# AD8428_shield.net
KiCad netlist of a schematic drawn in EAGLE
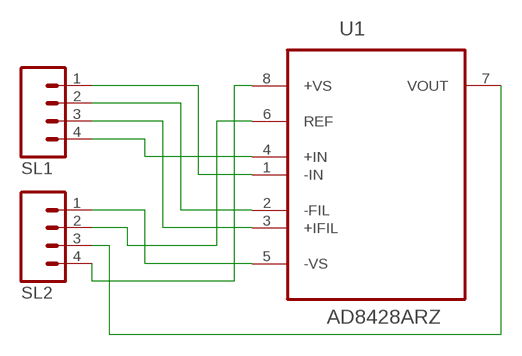
[diagram p0: schematic, sheet 1]

(export (version "E")
  (design (tool "Eeschema 10.0.6"))
  (components
    (comp (ref "SL1")
      (value "M04")
      (footprint "eagle-import:04P")
      (libsource (lib "eagle-import") (part "M04"))
    )
    (comp (ref "SL2")
      (value "M04")
      (footprint "eagle-import:04P")
      (libsource (lib "eagle-import") (part "M04"))
    )
    (comp (ref "U1")
      (value "AD8428ARZ")
      (footprint "eagle-import:SOIC127P600X175-8N")
      (libsource (lib "eagle-import") (part "AD8428ARZ"))
    )
  )
  (nets
    (net (code "1") (name "Net-(U1-+IFIL)") (class "Default")
      (node (ref "SL1") (pin "3") (pinfunction "3_3") (pintype "passive"))
      (node (ref "U1") (pin "3") (pinfunction "+IFIL_3") (pintype "input"))
    )
    (net (code "2") (name "Net-(U1-+IN)") (class "Default")
      (node (ref "SL1") (pin "4") (pinfunction "4_4") (pintype "passive"))
      (node (ref "U1") (pin "4") (pinfunction "+IN_4") (pintype "input"))
    )
    (net (code "3") (name "Net-(U1-+VS)") (class "Default")
      (node (ref "SL2") (pin "4") (pinfunction "4_4") (pintype "passive"))
      (node (ref "U1") (pin "8") (pinfunction "+VS_8") (pintype "power_in"))
    )
    (net (code "4") (name "Net-(U1--FIL)") (class "Default")
      (node (ref "SL1") (pin "2") (pinfunction "2_2") (pintype "passive"))
      (node (ref "U1") (pin "2") (pinfunction "-FIL_2") (pintype "input"))
    )
    (net (code "5") (name "Net-(U1--IN)") (class "Default")
      (node (ref "SL1") (pin "1") (pinfunction "1_1") (pintype "passive"))
      (node (ref "U1") (pin "1") (pinfunction "-IN_1") (pintype "input"))
    )
    (net (code "6") (name "Net-(U1--VS)") (class "Default")
      (node (ref "SL2") (pin "1") (pinfunction "1_1") (pintype "passive"))
      (node (ref "U1") (pin "5") (pinfunction "-VS_5") (pintype "power_in"))
    )
    (net (code "7") (name "Net-(U1-REF)") (class "Default")
      (node (ref "SL2") (pin "2") (pinfunction "2_2") (pintype "passive"))
      (node (ref "U1") (pin "6") (pinfunction "REF_6") (pintype "passive"))
    )
    (net (code "8") (name "Net-(U1-VOUT)") (class "Default")
      (node (ref "SL2") (pin "3") (pinfunction "3_3") (pintype "passive"))
      (node (ref "U1") (pin "7") (pinfunction "VOUT_7") (pintype "output"))
    )
  )
)
